# ProDocument_N64_SpyDVI_QSB_Compat_2024-0.net
KiCad netlist of a schematic drawn in EasyEDA Pro
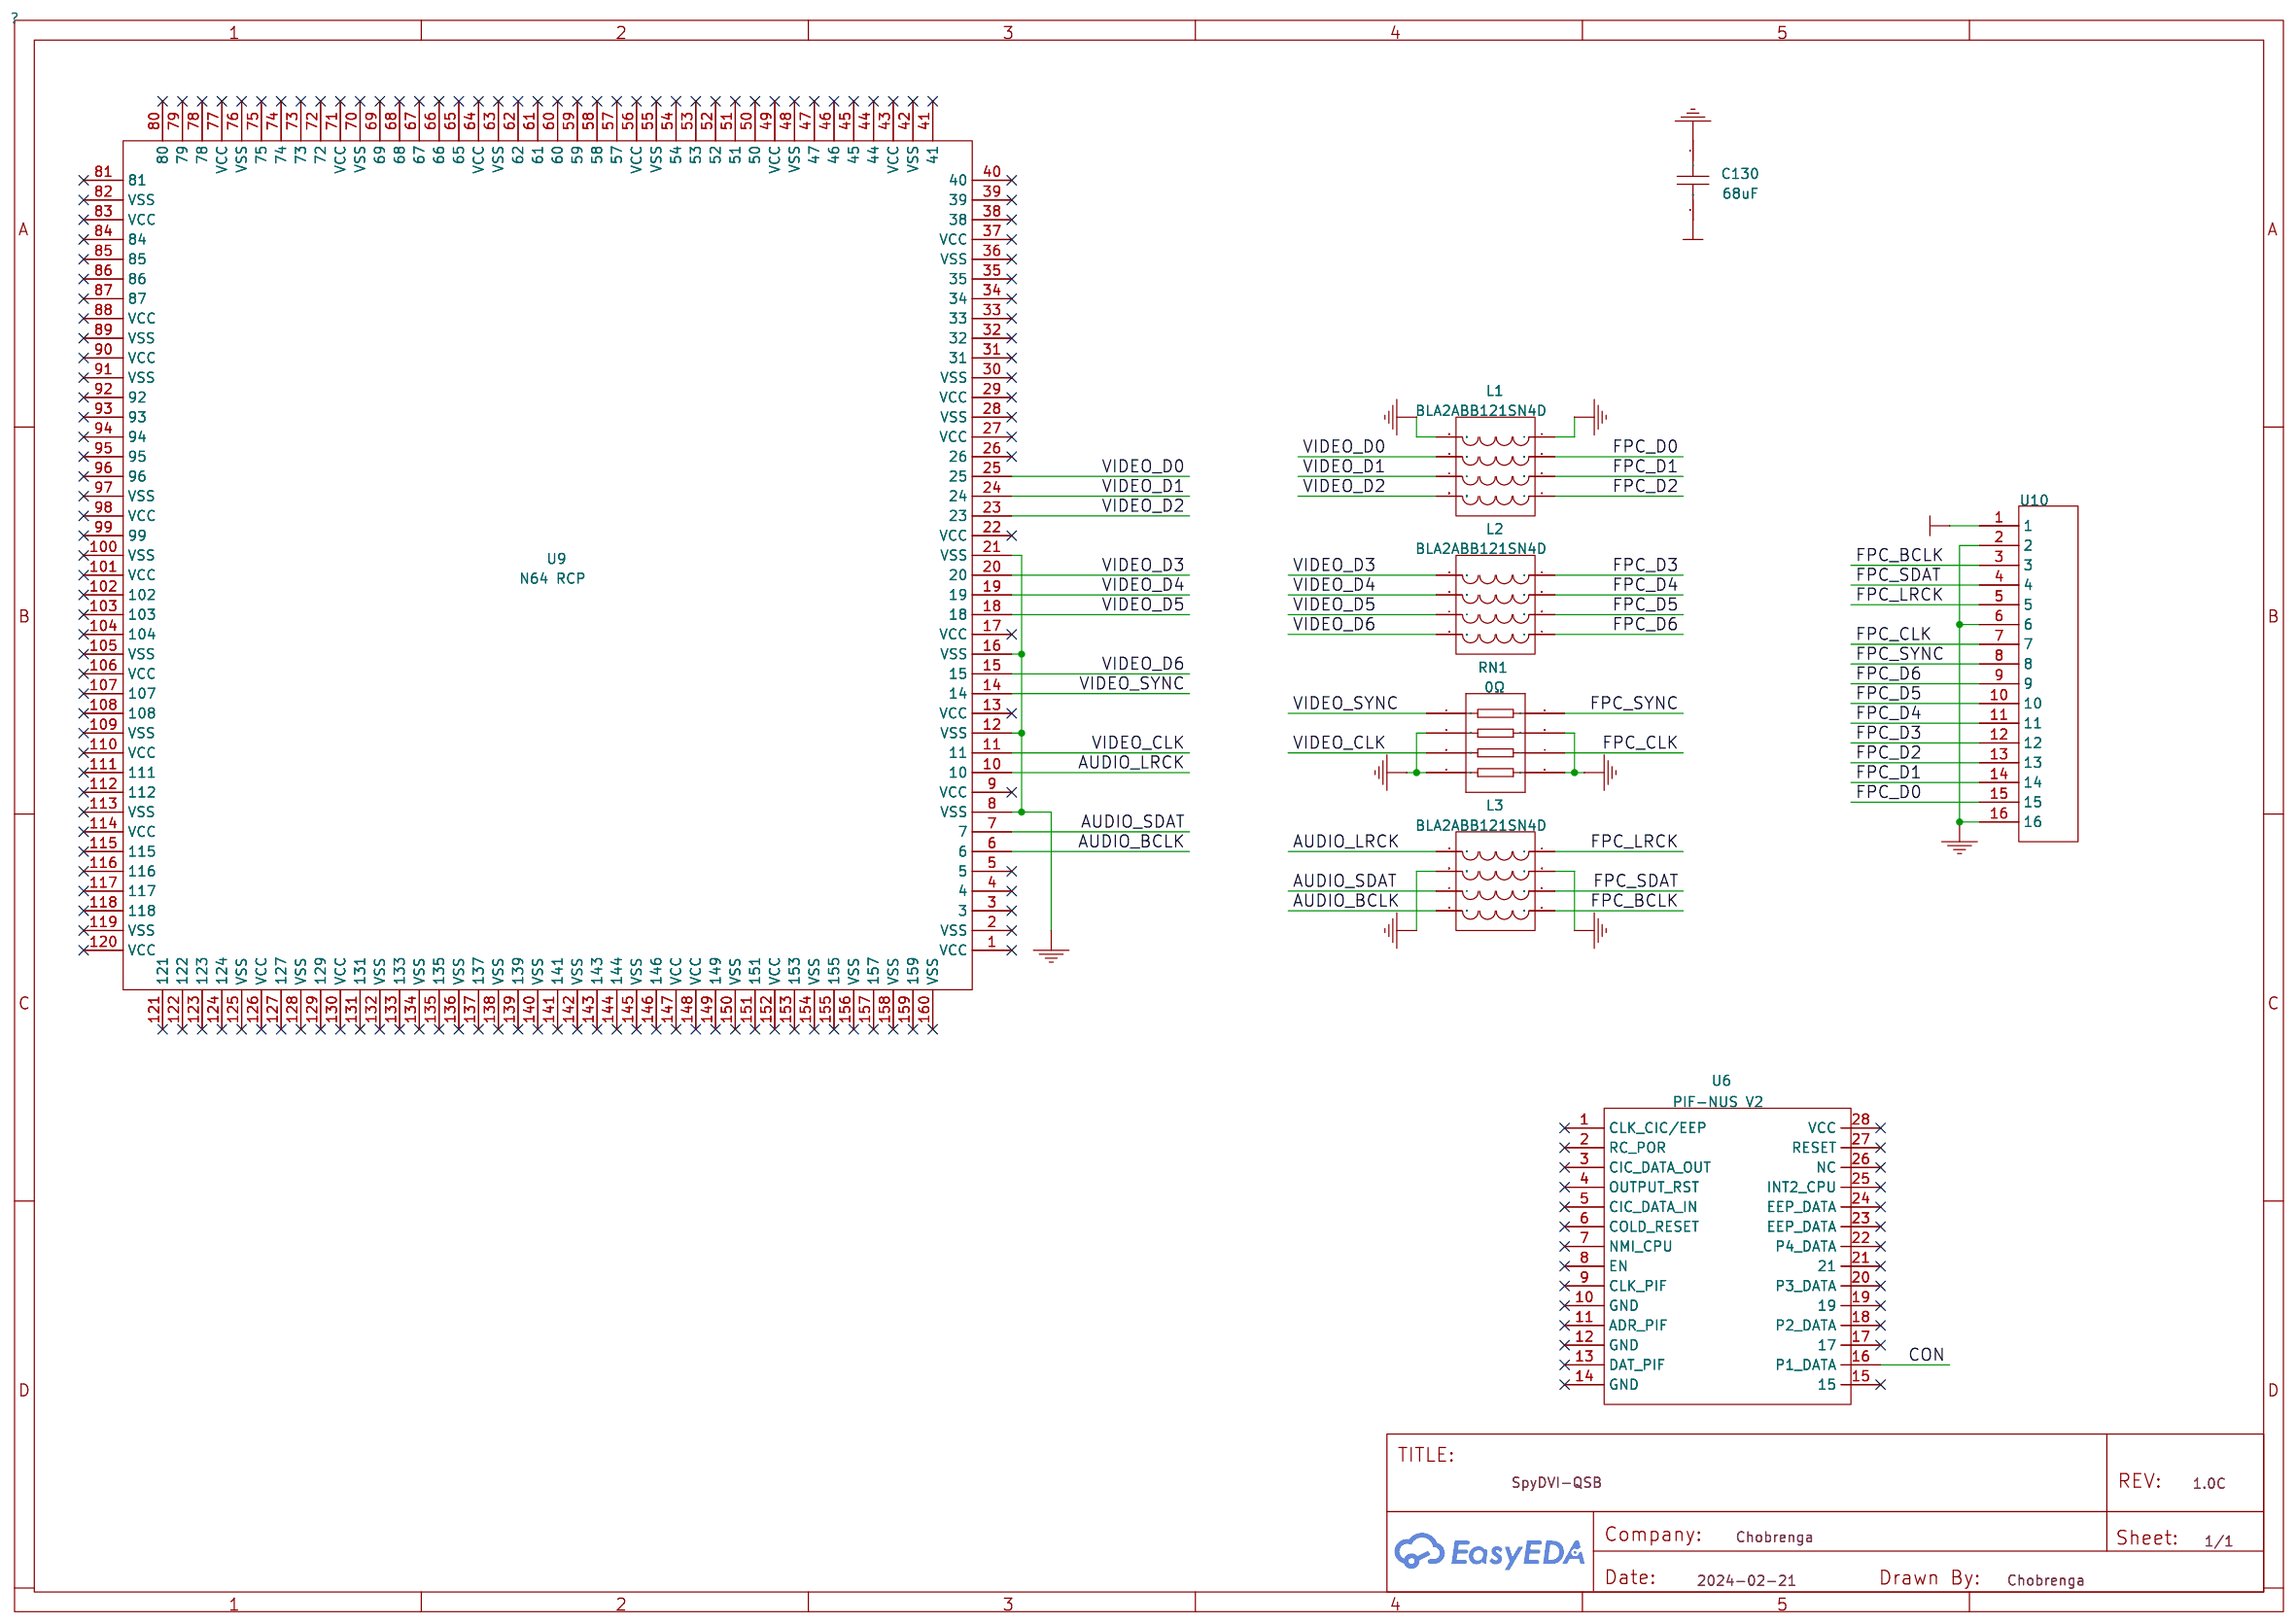
[diagram p0: schematic sheet]

(export (version "E")
  (design (tool "Eeschema 10.0.6"))
  (components
    (comp (ref "C130") (value "68uF") (libsource (lib "easyedapro") (part "68uF")))
    (comp (ref "L1")
      (value "BLA2ABB121SN4D")
      (footprint "easyedapro:BEAD-SMD_8P-L2.0-W1.0-P0.50-TL")
      (fields (field (name "Manufacturer") "muRata(村田)"))
      (libsource (lib "easyedapro") (part "BLA2ABB121SN4D"))
    )
    (comp (ref "L2")
      (value "BLA2ABB121SN4D")
      (footprint "easyedapro:BEAD-SMD_8P-L2.0-W1.0-P0.50-TL")
      (fields (field (name "Manufacturer") "muRata(村田)"))
      (libsource (lib "easyedapro") (part "BLA2ABB121SN4D"))
    )
    (comp (ref "L3")
      (value "BLA2ABB121SN4D")
      (footprint "easyedapro:BEAD-SMD_8P-L2.0-W1.0-P0.50-TL")
      (fields (field (name "Manufacturer") "muRata(村田)"))
      (libsource (lib "easyedapro") (part "BLA2ABB121SN4D"))
    )
    (comp (ref "RN1")
      (value "0Ω")
      (footprint "easyedapro:RES-ARRAY-SMD_0402-8P-L2.0-W1.0-BL")
      (fields (field (name "Manufacturer Part") "RC-MT08W000JT") (field (name "Manufacturer") "FH(风华)"))
      (libsource (lib "easyedapro") (part "0Ω"))
    )
    (comp (ref "U6") (value "PIF-NUS V2") (libsource (lib "easyedapro") (part "PIF-NUS V2")))
    (comp (ref "U9")
      (value "N64 RCP")
      (footprint "easyedapro:RCP NUS")
      (libsource (lib "easyedapro") (part "N64 RCP"))
    )
    (comp (ref "U10")
      (value "~")
      (description "For : AFA01-S16FCA-00")
      (libsource (lib "easyedapro") (part "16P_Ribbon"))
    )
  )
  (nets
    (net (code "1") (name "+5V") (class "Default")
      (node (ref "C130") (pin "2") (pinfunction "2_2") (pintype "unspecified"))
      (node (ref "U10") (pin "1") (pinfunction "1_1") (pintype "input"))
    )
    (net (code "2") (name "/AUDIO_BCLK") (class "Default")
      (node (ref "L3") (pin "8") (pinfunction "8_8") (pintype "unspecified"))
      (node (ref "U9") (pin "6") (pinfunction "6_6") (pintype "unspecified"))
    )
    (net (code "3") (name "/AUDIO_LRCK") (class "Default")
      (node (ref "L3") (pin "5") (pinfunction "5_5") (pintype "unspecified"))
      (node (ref "U9") (pin "10") (pinfunction "10_10") (pintype "unspecified"))
    )
    (net (code "4") (name "/AUDIO_SDAT") (class "Default")
      (node (ref "L3") (pin "7") (pinfunction "7_7") (pintype "unspecified"))
      (node (ref "U9") (pin "7") (pinfunction "7_7") (pintype "unspecified"))
    )
    (net (code "5") (name "/CON") (class "Default")
      (node (ref "U6") (pin "16") (pinfunction "P1_DATA_16") (pintype "unspecified"))
    )
    (net (code "6") (name "/FPC_BCLK") (class "Default")
      (node (ref "L3") (pin "1") (pinfunction "1_1") (pintype "unspecified"))
      (node (ref "U10") (pin "3") (pinfunction "3_3") (pintype "input"))
    )
    (net (code "7") (name "/FPC_CLK") (class "Default")
      (node (ref "RN1") (pin "7") (pinfunction "7_7") (pintype "input"))
      (node (ref "U10") (pin "7") (pinfunction "7_7") (pintype "input"))
    )
    (net (code "8") (name "/FPC_D0") (class "Default")
      (node (ref "L1") (pin "3") (pinfunction "3_3") (pintype "unspecified"))
      (node (ref "U10") (pin "15") (pinfunction "15_15") (pintype "input"))
    )
    (net (code "9") (name "/FPC_D1") (class "Default")
      (node (ref "L1") (pin "2") (pinfunction "2_2") (pintype "unspecified"))
      (node (ref "U10") (pin "14") (pinfunction "14_14") (pintype "input"))
    )
    (net (code "10") (name "/FPC_D2") (class "Default")
      (node (ref "L1") (pin "1") (pinfunction "1_1") (pintype "unspecified"))
      (node (ref "U10") (pin "13") (pinfunction "13_13") (pintype "input"))
    )
    (net (code "11") (name "/FPC_D3") (class "Default")
      (node (ref "L2") (pin "4") (pinfunction "4_4") (pintype "unspecified"))
      (node (ref "U10") (pin "12") (pinfunction "12_12") (pintype "input"))
    )
    (net (code "12") (name "/FPC_D4") (class "Default")
      (node (ref "L2") (pin "3") (pinfunction "3_3") (pintype "unspecified"))
      (node (ref "U10") (pin "11") (pinfunction "11_11") (pintype "input"))
    )
    (net (code "13") (name "/FPC_D5") (class "Default")
      (node (ref "L2") (pin "2") (pinfunction "2_2") (pintype "unspecified"))
      (node (ref "U10") (pin "10") (pinfunction "10_10") (pintype "input"))
    )
    (net (code "14") (name "/FPC_D6") (class "Default")
      (node (ref "L2") (pin "1") (pinfunction "1_1") (pintype "unspecified"))
      (node (ref "U10") (pin "9") (pinfunction "9_9") (pintype "input"))
    )
    (net (code "15") (name "/FPC_LRCK") (class "Default")
      (node (ref "L3") (pin "4") (pinfunction "4_4") (pintype "unspecified"))
      (node (ref "U10") (pin "5") (pinfunction "5_5") (pintype "input"))
    )
    (net (code "16") (name "/FPC_SDAT") (class "Default")
      (node (ref "L3") (pin "2") (pinfunction "2_2") (pintype "unspecified"))
      (node (ref "U10") (pin "4") (pinfunction "4_4") (pintype "input"))
    )
    (net (code "17") (name "/FPC_SYNC") (class "Default")
      (node (ref "RN1") (pin "5") (pinfunction "5_5") (pintype "input"))
      (node (ref "U10") (pin "8") (pinfunction "8_8") (pintype "input"))
    )
    (net (code "18") (name "/VIDEO_CLK") (class "Default")
      (node (ref "RN1") (pin "2") (pinfunction "2_2") (pintype "input"))
      (node (ref "U9") (pin "11") (pinfunction "11_11") (pintype "unspecified"))
    )
    (net (code "19") (name "/VIDEO_D0") (class "Default")
      (node (ref "L1") (pin "6") (pinfunction "6_6") (pintype "unspecified"))
      (node (ref "U9") (pin "25") (pinfunction "25_25") (pintype "unspecified"))
    )
    (net (code "20") (name "/VIDEO_D1") (class "Default")
      (node (ref "L1") (pin "7") (pinfunction "7_7") (pintype "unspecified"))
      (node (ref "U9") (pin "24") (pinfunction "24_24") (pintype "unspecified"))
    )
    (net (code "21") (name "/VIDEO_D2") (class "Default")
      (node (ref "L1") (pin "8") (pinfunction "8_8") (pintype "unspecified"))
      (node (ref "U9") (pin "23") (pinfunction "23_23") (pintype "unspecified"))
    )
    (net (code "22") (name "/VIDEO_D3") (class "Default")
      (node (ref "L2") (pin "5") (pinfunction "5_5") (pintype "unspecified"))
      (node (ref "U9") (pin "20") (pinfunction "20_20") (pintype "unspecified"))
    )
    (net (code "23") (name "/VIDEO_D4") (class "Default")
      (node (ref "L2") (pin "6") (pinfunction "6_6") (pintype "unspecified"))
      (node (ref "U9") (pin "19") (pinfunction "19_19") (pintype "unspecified"))
    )
    (net (code "24") (name "/VIDEO_D5") (class "Default")
      (node (ref "L2") (pin "7") (pinfunction "7_7") (pintype "unspecified"))
      (node (ref "U9") (pin "18") (pinfunction "18_18") (pintype "unspecified"))
    )
    (net (code "25") (name "/VIDEO_D6") (class "Default")
      (node (ref "L2") (pin "8") (pinfunction "8_8") (pintype "unspecified"))
      (node (ref "U9") (pin "15") (pinfunction "15_15") (pintype "unspecified"))
    )
    (net (code "26") (name "/VIDEO_SYNC") (class "Default")
      (node (ref "RN1") (pin "4") (pinfunction "4_4") (pintype "input"))
      (node (ref "U9") (pin "14") (pinfunction "14_14") (pintype "unspecified"))
    )
    (net (code "27") (name "GND") (class "Default")
      (node (ref "C130") (pin "1") (pinfunction "1_1") (pintype "unspecified"))
      (node (ref "L1") (pin "4") (pinfunction "4_4") (pintype "unspecified"))
      (node (ref "L1") (pin "5") (pinfunction "5_5") (pintype "unspecified"))
      (node (ref "L3") (pin "3") (pinfunction "3_3") (pintype "unspecified"))
      (node (ref "L3") (pin "6") (pinfunction "6_6") (pintype "unspecified"))
      (node (ref "RN1") (pin "1") (pinfunction "1_1") (pintype "input"))
      (node (ref "RN1") (pin "3") (pinfunction "3_3") (pintype "input"))
      (node (ref "RN1") (pin "6") (pinfunction "6_6") (pintype "input"))
      (node (ref "RN1") (pin "8") (pinfunction "8_8") (pintype "input"))
      (node (ref "U10") (pin "16") (pinfunction "16_16") (pintype "input"))
      (node (ref "U10") (pin "2") (pinfunction "2_2") (pintype "input"))
      (node (ref "U10") (pin "6") (pinfunction "6_6") (pintype "input"))
      (node (ref "U9") (pin "12") (pinfunction "VSS_12") (pintype "unspecified"))
      (node (ref "U9") (pin "16") (pinfunction "VSS_16") (pintype "unspecified"))
      (node (ref "U9") (pin "21") (pinfunction "VSS_21") (pintype "unspecified"))
      (node (ref "U9") (pin "8") (pinfunction "VSS_8") (pintype "unspecified"))
    )
    (net (code "28") (name "unconnected-(U6-ADR_PIF-Pad11)") (class "Default")
      (node (ref "U6") (pin "11") (pinfunction "ADR_PIF_11") (pintype "unspecified+no_connect"))
    )
    (net (code "29") (name "unconnected-(U6-CIC_DATA_IN-Pad5)") (class "Default")
      (node (ref "U6") (pin "5") (pinfunction "CIC_DATA_IN_5") (pintype "unspecified+no_connect"))
    )
    (net (code "30") (name "unconnected-(U6-CIC_DATA_OUT-Pad3)") (class "Default")
      (node (ref "U6") (pin "3") (pinfunction "CIC_DATA_OUT_3") (pintype "unspecified+no_connect"))
    )
    (net (code "31") (name "unconnected-(U6-CLK_CIC{slash}EEP-Pad1)") (class "Default")
      (node (ref "U6") (pin "1") (pinfunction "CLK_CIC/EEP_1") (pintype "unspecified+no_connect"))
    )
    (net (code "32") (name "unconnected-(U6-CLK_PIF-Pad9)") (class "Default")
      (node (ref "U6") (pin "9") (pinfunction "CLK_PIF_9") (pintype "unspecified+no_connect"))
    )
    (net (code "33") (name "unconnected-(U6-COLD_RESET-Pad6)") (class "Default")
      (node (ref "U6") (pin "6") (pinfunction "COLD_RESET_6") (pintype "unspecified+no_connect"))
    )
    (net (code "34") (name "unconnected-(U6-DAT_PIF-Pad13)") (class "Default")
      (node (ref "U6") (pin "13") (pinfunction "DAT_PIF_13") (pintype "unspecified+no_connect"))
    )
    (net (code "35") (name "unconnected-(U6-EEP_DATA-Pad23)") (class "Default")
      (node (ref "U6") (pin "23") (pinfunction "EEP_DATA_23") (pintype "unspecified+no_connect"))
    )
    (net (code "36") (name "unconnected-(U6-EEP_DATA-Pad24)") (class "Default")
      (node (ref "U6") (pin "24") (pinfunction "EEP_DATA_24") (pintype "unspecified+no_connect"))
    )
    (net (code "37") (name "unconnected-(U6-EN-Pad8)") (class "Default")
      (node (ref "U6") (pin "8") (pinfunction "EN_8") (pintype "unspecified+no_connect"))
    )
    (net (code "38") (name "unconnected-(U6-GND-Pad10)") (class "Default")
      (node (ref "U6") (pin "10") (pinfunction "GND_10") (pintype "unspecified+no_connect"))
    )
    (net (code "39") (name "unconnected-(U6-GND-Pad12)") (class "Default")
      (node (ref "U6") (pin "12") (pinfunction "GND_12") (pintype "unspecified+no_connect"))
    )
    (net (code "40") (name "unconnected-(U6-GND-Pad14)") (class "Default")
      (node (ref "U6") (pin "14") (pinfunction "GND_14") (pintype "unspecified+no_connect"))
    )
    (net (code "41") (name "unconnected-(U6-INT2_CPU-Pad25)") (class "Default")
      (node (ref "U6") (pin "25") (pinfunction "INT2_CPU_25") (pintype "unspecified+no_connect"))
    )
    (net (code "42") (name "unconnected-(U6-NC-Pad26)") (class "Default")
      (node (ref "U6") (pin "26") (pinfunction "NC_26") (pintype "unspecified+no_connect"))
    )
    (net (code "43") (name "unconnected-(U6-NMI_CPU-Pad7)") (class "Default")
      (node (ref "U6") (pin "7") (pinfunction "NMI_CPU_7") (pintype "unspecified+no_connect"))
    )
    (net (code "44") (name "unconnected-(U6-OUTPUT_RST-Pad4)") (class "Default")
      (node (ref "U6") (pin "4") (pinfunction "OUTPUT_RST_4") (pintype "unspecified+no_connect"))
    )
    (net (code "45") (name "unconnected-(U6-P2_DATA-Pad18)") (class "Default")
      (node (ref "U6") (pin "18") (pinfunction "P2_DATA_18") (pintype "unspecified+no_connect"))
    )
    (net (code "46") (name "unconnected-(U6-P3_DATA-Pad20)") (class "Default")
      (node (ref "U6") (pin "20") (pinfunction "P3_DATA_20") (pintype "unspecified+no_connect"))
    )
    (net (code "47") (name "unconnected-(U6-P4_DATA-Pad22)") (class "Default")
      (node (ref "U6") (pin "22") (pinfunction "P4_DATA_22") (pintype "unspecified+no_connect"))
    )
    (net (code "48") (name "unconnected-(U6-Pad15)") (class "Default")
      (node (ref "U6") (pin "15") (pinfunction "15_15") (pintype "unspecified+no_connect"))
    )
    (net (code "49") (name "unconnected-(U6-Pad17)") (class "Default")
      (node (ref "U6") (pin "17") (pinfunction "17_17") (pintype "unspecified+no_connect"))
    )
    (net (code "50") (name "unconnected-(U6-Pad19)") (class "Default")
      (node (ref "U6") (pin "19") (pinfunction "19_19") (pintype "unspecified+no_connect"))
    )
    (net (code "51") (name "unconnected-(U6-Pad21)") (class "Default")
      (node (ref "U6") (pin "21") (pinfunction "21_21") (pintype "unspecified+no_connect"))
    )
    (net (code "52") (name "unconnected-(U6-RC_POR-Pad2)") (class "Default")
      (node (ref "U6") (pin "2") (pinfunction "RC_POR_2") (pintype "unspecified+no_connect"))
    )
    (net (code "53") (name "unconnected-(U6-RESET-Pad27)") (class "Default")
      (node (ref "U6") (pin "27") (pinfunction "RESET_27") (pintype "unspecified+no_connect"))
    )
    (net (code "54") (name "unconnected-(U6-VCC-Pad28)") (class "Default")
      (node (ref "U6") (pin "28") (pinfunction "VCC_28") (pintype "unspecified+no_connect"))
    )
    (net (code "55") (name "unconnected-(U9-Pad3)") (class "Default")
      (node (ref "U9") (pin "3") (pinfunction "3_3") (pintype "unspecified+no_connect"))
    )
    (net (code "56") (name "unconnected-(U9-Pad4)") (class "Default")
      (node (ref "U9") (pin "4") (pinfunction "4_4") (pintype "unspecified+no_connect"))
    )
    (net (code "57") (name "unconnected-(U9-Pad5)") (class "Default")
      (node (ref "U9") (pin "5") (pinfunction "5_5") (pintype "unspecified+no_connect"))
    )
    (net (code "58") (name "unconnected-(U9-Pad26)") (class "Default")
      (node (ref "U9") (pin "26") (pinfunction "26_26") (pintype "unspecified+no_connect"))
    )
    (net (code "59") (name "unconnected-(U9-Pad31)") (class "Default")
      (node (ref "U9") (pin "31") (pinfunction "31_31") (pintype "unspecified+no_connect"))
    )
    (net (code "60") (name "unconnected-(U9-Pad32)") (class "Default")
      (node (ref "U9") (pin "32") (pinfunction "32_32") (pintype "unspecified+no_connect"))
    )
    (net (code "61") (name "unconnected-(U9-Pad33)") (class "Default")
      (node (ref "U9") (pin "33") (pinfunction "33_33") (pintype "unspecified+no_connect"))
    )
    (net (code "62") (name "unconnected-(U9-Pad34)") (class "Default")
      (node (ref "U9") (pin "34") (pinfunction "34_34") (pintype "unspecified+no_connect"))
    )
    (net (code "63") (name "unconnected-(U9-Pad35)") (class "Default")
      (node (ref "U9") (pin "35") (pinfunction "35_35") (pintype "unspecified+no_connect"))
    )
    (net (code "64") (name "unconnected-(U9-Pad38)") (class "Default")
      (node (ref "U9") (pin "38") (pinfunction "38_38") (pintype "unspecified+no_connect"))
    )
    (net (code "65") (name "unconnected-(U9-Pad39)") (class "Default")
      (node (ref "U9") (pin "39") (pinfunction "39_39") (pintype "unspecified+no_connect"))
    )
    (net (code "66") (name "unconnected-(U9-Pad40)") (class "Default")
      (node (ref "U9") (pin "40") (pinfunction "40_40") (pintype "unspecified+no_connect"))
    )
    (net (code "67") (name "unconnected-(U9-Pad41)") (class "Default")
      (node (ref "U9") (pin "41") (pinfunction "41_41") (pintype "unspecified+no_connect"))
    )
    (net (code "68") (name "unconnected-(U9-Pad44)") (class "Default")
      (node (ref "U9") (pin "44") (pinfunction "44_44") (pintype "unspecified+no_connect"))
    )
    (net (code "69") (name "unconnected-(U9-Pad45)") (class "Default")
      (node (ref "U9") (pin "45") (pinfunction "45_45") (pintype "unspecified+no_connect"))
    )
    (net (code "70") (name "unconnected-(U9-Pad46)") (class "Default")
      (node (ref "U9") (pin "46") (pinfunction "46_46") (pintype "unspecified+no_connect"))
    )
    (net (code "71") (name "unconnected-(U9-Pad47)") (class "Default")
      (node (ref "U9") (pin "47") (pinfunction "47_47") (pintype "unspecified+no_connect"))
    )
    (net (code "72") (name "unconnected-(U9-Pad50)") (class "Default")
      (node (ref "U9") (pin "50") (pinfunction "50_50") (pintype "unspecified+no_connect"))
    )
    (net (code "73") (name "unconnected-(U9-Pad51)") (class "Default")
      (node (ref "U9") (pin "51") (pinfunction "51_51") (pintype "unspecified+no_connect"))
    )
    (net (code "74") (name "unconnected-(U9-Pad52)") (class "Default")
      (node (ref "U9") (pin "52") (pinfunction "52_52") (pintype "unspecified+no_connect"))
    )
    (net (code "75") (name "unconnected-(U9-Pad53)") (class "Default")
      (node (ref "U9") (pin "53") (pinfunction "53_53") (pintype "unspecified+no_connect"))
    )
    (net (code "76") (name "unconnected-(U9-Pad54)") (class "Default")
      (node (ref "U9") (pin "54") (pinfunction "54_54") (pintype "unspecified+no_connect"))
    )
    (net (code "77") (name "unconnected-(U9-Pad57)") (class "Default")
      (node (ref "U9") (pin "57") (pinfunction "57_57") (pintype "unspecified+no_connect"))
    )
    (net (code "78") (name "unconnected-(U9-Pad58)") (class "Default")
      (node (ref "U9") (pin "58") (pinfunction "58_58") (pintype "unspecified+no_connect"))
    )
    (net (code "79") (name "unconnected-(U9-Pad59)") (class "Default")
      (node (ref "U9") (pin "59") (pinfunction "59_59") (pintype "unspecified+no_connect"))
    )
    (net (code "80") (name "unconnected-(U9-Pad60)") (class "Default")
      (node (ref "U9") (pin "60") (pinfunction "60_60") (pintype "unspecified+no_connect"))
    )
    (net (code "81") (name "unconnected-(U9-Pad61)") (class "Default")
      (node (ref "U9") (pin "61") (pinfunction "61_61") (pintype "unspecified+no_connect"))
    )
    (net (code "82") (name "unconnected-(U9-Pad62)") (class "Default")
      (node (ref "U9") (pin "62") (pinfunction "62_62") (pintype "unspecified+no_connect"))
    )
    (net (code "83") (name "unconnected-(U9-Pad65)") (class "Default")
      (node (ref "U9") (pin "65") (pinfunction "65_65") (pintype "unspecified+no_connect"))
    )
    (net (code "84") (name "unconnected-(U9-Pad66)") (class "Default")
      (node (ref "U9") (pin "66") (pinfunction "66_66") (pintype "unspecified+no_connect"))
    )
    (net (code "85") (name "unconnected-(U9-Pad67)") (class "Default")
      (node (ref "U9") (pin "67") (pinfunction "67_67") (pintype "unspecified+no_connect"))
    )
    (net (code "86") (name "unconnected-(U9-Pad68)") (class "Default")
      (node (ref "U9") (pin "68") (pinfunction "68_68") (pintype "unspecified+no_connect"))
    )
    (net (code "87") (name "unconnected-(U9-Pad69)") (class "Default")
      (node (ref "U9") (pin "69") (pinfunction "69_69") (pintype "unspecified+no_connect"))
    )
    (net (code "88") (name "unconnected-(U9-Pad72)") (class "Default")
      (node (ref "U9") (pin "72") (pinfunction "72_72") (pintype "unspecified+no_connect"))
    )
    (net (code "89") (name "unconnected-(U9-Pad73)") (class "Default")
      (node (ref "U9") (pin "73") (pinfunction "73_73") (pintype "unspecified+no_connect"))
    )
    (net (code "90") (name "unconnected-(U9-Pad74)") (class "Default")
      (node (ref "U9") (pin "74") (pinfunction "74_74") (pintype "unspecified+no_connect"))
    )
    (net (code "91") (name "unconnected-(U9-Pad75)") (class "Default")
      (node (ref "U9") (pin "75") (pinfunction "75_75") (pintype "unspecified+no_connect"))
    )
    (net (code "92") (name "unconnected-(U9-Pad78)") (class "Default")
      (node (ref "U9") (pin "78") (pinfunction "78_78") (pintype "unspecified+no_connect"))
    )
    (net (code "93") (name "unconnected-(U9-Pad79)") (class "Default")
      (node (ref "U9") (pin "79") (pinfunction "79_79") (pintype "unspecified+no_connect"))
    )
    (net (code "94") (name "unconnected-(U9-Pad80)") (class "Default")
      (node (ref "U9") (pin "80") (pinfunction "80_80") (pintype "unspecified+no_connect"))
    )
    (net (code "95") (name "unconnected-(U9-Pad81)") (class "Default")
      (node (ref "U9") (pin "81") (pinfunction "81_81") (pintype "unspecified+no_connect"))
    )
    (net (code "96") (name "unconnected-(U9-Pad84)") (class "Default")
      (node (ref "U9") (pin "84") (pinfunction "84_84") (pintype "unspecified+no_connect"))
    )
    (net (code "97") (name "unconnected-(U9-Pad85)") (class "Default")
      (node (ref "U9") (pin "85") (pinfunction "85_85") (pintype "unspecified+no_connect"))
    )
    (net (code "98") (name "unconnected-(U9-Pad86)") (class "Default")
      (node (ref "U9") (pin "86") (pinfunction "86_86") (pintype "unspecified+no_connect"))
    )
    (net (code "99") (name "unconnected-(U9-Pad87)") (class "Default")
      (node (ref "U9") (pin "87") (pinfunction "87_87") (pintype "unspecified+no_connect"))
    )
    (net (code "100") (name "unconnected-(U9-Pad92)") (class "Default")
      (node (ref "U9") (pin "92") (pinfunction "92_92") (pintype "unspecified+no_connect"))
    )
    (net (code "101") (name "unconnected-(U9-Pad93)") (class "Default")
      (node (ref "U9") (pin "93") (pinfunction "93_93") (pintype "unspecified+no_connect"))
    )
    (net (code "102") (name "unconnected-(U9-Pad94)") (class "Default")
      (node (ref "U9") (pin "94") (pinfunction "94_94") (pintype "unspecified+no_connect"))
    )
    (net (code "103") (name "unconnected-(U9-Pad95)") (class "Default")
      (node (ref "U9") (pin "95") (pinfunction "95_95") (pintype "unspecified+no_connect"))
    )
    (net (code "104") (name "unconnected-(U9-Pad96)") (class "Default")
      (node (ref "U9") (pin "96") (pinfunction "96_96") (pintype "unspecified+no_connect"))
    )
    (net (code "105") (name "unconnected-(U9-Pad99)") (class "Default")
      (node (ref "U9") (pin "99") (pinfunction "99_99") (pintype "unspecified+no_connect"))
    )
    (net (code "106") (name "unconnected-(U9-Pad102)") (class "Default")
      (node (ref "U9") (pin "102") (pinfunction "102_102") (pintype "unspecified+no_connect"))
    )
    (net (code "107") (name "unconnected-(U9-Pad103)") (class "Default")
      (node (ref "U9") (pin "103") (pinfunction "103_103") (pintype "unspecified+no_connect"))
    )
    (net (code "108") (name "unconnected-(U9-Pad104)") (class "Default")
      (node (ref "U9") (pin "104") (pinfunction "104_104") (pintype "unspecified+no_connect"))
    )
    (net (code "109") (name "unconnected-(U9-Pad107)") (class "Default")
      (node (ref "U9") (pin "107") (pinfunction "107_107") (pintype "unspecified+no_connect"))
    )
    (net (code "110") (name "unconnected-(U9-Pad108)") (class "Default")
      (node (ref "U9") (pin "108") (pinfunction "108_108") (pintype "unspecified+no_connect"))
    )
    (net (code "111") (name "unconnected-(U9-Pad111)") (class "Default")
      (node (ref "U9") (pin "111") (pinfunction "111_111") (pintype "unspecified+no_connect"))
    )
    (net (code "112") (name "unconnected-(U9-Pad112)") (class "Default")
      (node (ref "U9") (pin "112") (pinfunction "112_112") (pintype "unspecified+no_connect"))
    )
    (net (code "113") (name "unconnected-(U9-Pad115)") (class "Default")
      (node (ref "U9") (pin "115") (pinfunction "115_115") (pintype "unspecified+no_connect"))
    )
    (net (code "114") (name "unconnected-(U9-Pad116)") (class "Default")
      (node (ref "U9") (pin "116") (pinfunction "116_116") (pintype "unspecified+no_connect"))
    )
    (net (code "115") (name "unconnected-(U9-Pad117)") (class "Default")
      (node (ref "U9") (pin "117") (pinfunction "117_117") (pintype "unspecified+no_connect"))
    )
    (net (code "116") (name "unconnected-(U9-Pad118)") (class "Default")
      (node (ref "U9") (pin "118") (pinfunction "118_118") (pintype "unspecified+no_connect"))
    )
    (net (code "117") (name "unconnected-(U9-Pad121)") (class "Default")
      (node (ref "U9") (pin "121") (pinfunction "121_121") (pintype "unspecified+no_connect"))
    )
    (net (code "118") (name "unconnected-(U9-Pad122)") (class "Default")
      (node (ref "U9") (pin "122") (pinfunction "122_122") (pintype "unspecified+no_connect"))
    )
    (net (code "119") (name "unconnected-(U9-Pad123)") (class "Default")
      (node (ref "U9") (pin "123") (pinfunction "123_123") (pintype "unspecified+no_connect"))
    )
    (net (code "120") (name "unconnected-(U9-Pad124)") (class "Default")
      (node (ref "U9") (pin "124") (pinfunction "124_124") (pintype "unspecified+no_connect"))
    )
    (net (code "121") (name "unconnected-(U9-Pad127)") (class "Default")
      (node (ref "U9") (pin "127") (pinfunction "127_127") (pintype "unspecified+no_connect"))
    )
    (net (code "122") (name "unconnected-(U9-Pad129)") (class "Default")
      (node (ref "U9") (pin "129") (pinfunction "129_129") (pintype "unspecified+no_connect"))
    )
    (net (code "123") (name "unconnected-(U9-Pad131)") (class "Default")
      (node (ref "U9") (pin "131") (pinfunction "131_131") (pintype "unspecified+no_connect"))
    )
    (net (code "124") (name "unconnected-(U9-Pad133)") (class "Default")
      (node (ref "U9") (pin "133") (pinfunction "133_133") (pintype "unspecified+no_connect"))
    )
    (net (code "125") (name "unconnected-(U9-Pad135)") (class "Default")
      (node (ref "U9") (pin "135") (pinfunction "135_135") (pintype "unspecified+no_connect"))
    )
    (net (code "126") (name "unconnected-(U9-Pad137)") (class "Default")
      (node (ref "U9") (pin "137") (pinfunction "137_137") (pintype "unspecified+no_connect"))
    )
    (net (code "127") (name "unconnected-(U9-Pad139)") (class "Default")
      (node (ref "U9") (pin "139") (pinfunction "139_139") (pintype "unspecified+no_connect"))
    )
    (net (code "128") (name "unconnected-(U9-Pad141)") (class "Default")
      (node (ref "U9") (pin "141") (pinfunction "141_141") (pintype "unspecified+no_connect"))
    )
    (net (code "129") (name "unconnected-(U9-Pad143)") (class "Default")
      (node (ref "U9") (pin "143") (pinfunction "143_143") (pintype "unspecified+no_connect"))
    )
    (net (code "130") (name "unconnected-(U9-Pad144)") (class "Default")
      (node (ref "U9") (pin "144") (pinfunction "144_144") (pintype "unspecified+no_connect"))
    )
    (net (code "131") (name "unconnected-(U9-Pad146)") (class "Default")
      (node (ref "U9") (pin "146") (pinfunction "146_146") (pintype "unspecified+no_connect"))
    )
    (net (code "132") (name "unconnected-(U9-Pad149)") (class "Default")
      (node (ref "U9") (pin "149") (pinfunction "149_149") (pintype "unspecified+no_connect"))
    )
    (net (code "133") (name "unconnected-(U9-Pad151)") (class "Default")
      (node (ref "U9") (pin "151") (pinfunction "151_151") (pintype "unspecified+no_connect"))
    )
    (net (code "134") (name "unconnected-(U9-Pad153)") (class "Default")
      (node (ref "U9") (pin "153") (pinfunction "153_153") (pintype "unspecified+no_connect"))
    )
    (net (code "135") (name "unconnected-(U9-Pad155)") (class "Default")
      (node (ref "U9") (pin "155") (pinfunction "155_155") (pintype "unspecified+no_connect"))
    )
    (net (code "136") (name "unconnected-(U9-Pad157)") (class "Default")
      (node (ref "U9") (pin "157") (pinfunction "157_157") (pintype "unspecified+no_connect"))
    )
    (net (code "137") (name "unconnected-(U9-Pad159)") (class "Default")
      (node (ref "U9") (pin "159") (pinfunction "159_159") (pintype "unspecified+no_connect"))
    )
    (net (code "138") (name "unconnected-(U9-VCC-Pad1)") (class "Default")
      (node (ref "U9") (pin "1") (pinfunction "VCC_1") (pintype "unspecified+no_connect"))
    )
    (net (code "139") (name "unconnected-(U9-VCC-Pad9)") (class "Default")
      (node (ref "U9") (pin "9") (pinfunction "VCC_9") (pintype "unspecified+no_connect"))
    )
    (net (code "140") (name "unconnected-(U9-VCC-Pad13)") (class "Default")
      (node (ref "U9") (pin "13") (pinfunction "VCC_13") (pintype "unspecified+no_connect"))
    )
    (net (code "141") (name "unconnected-(U9-VCC-Pad17)") (class "Default")
      (node (ref "U9") (pin "17") (pinfunction "VCC_17") (pintype "unspecified+no_connect"))
    )
    (net (code "142") (name "unconnected-(U9-VCC-Pad22)") (class "Default")
      (node (ref "U9") (pin "22") (pinfunction "VCC_22") (pintype "unspecified+no_connect"))
    )
    (net (code "143") (name "unconnected-(U9-VCC-Pad27)") (class "Default")
      (node (ref "U9") (pin "27") (pinfunction "VCC_27") (pintype "unspecified+no_connect"))
    )
    (net (code "144") (name "unconnected-(U9-VCC-Pad29)") (class "Default")
      (node (ref "U9") (pin "29") (pinfunction "VCC_29") (pintype "unspecified+no_connect"))
    )
    (net (code "145") (name "unconnected-(U9-VCC-Pad37)") (class "Default")
      (node (ref "U9") (pin "37") (pinfunction "VCC_37") (pintype "unspecified+no_connect"))
    )
    (net (code "146") (name "unconnected-(U9-VCC-Pad43)") (class "Default")
      (node (ref "U9") (pin "43") (pinfunction "VCC_43") (pintype "unspecified+no_connect"))
    )
    (net (code "147") (name "unconnected-(U9-VCC-Pad49)") (class "Default")
      (node (ref "U9") (pin "49") (pinfunction "VCC_49") (pintype "unspecified+no_connect"))
    )
    (net (code "148") (name "unconnected-(U9-VCC-Pad56)") (class "Default")
      (node (ref "U9") (pin "56") (pinfunction "VCC_56") (pintype "unspecified+no_connect"))
    )
    (net (code "149") (name "unconnected-(U9-VCC-Pad64)") (class "Default")
      (node (ref "U9") (pin "64") (pinfunction "VCC_64") (pintype "unspecified+no_connect"))
    )
    (net (code "150") (name "unconnected-(U9-VCC-Pad71)") (class "Default")
      (node (ref "U9") (pin "71") (pinfunction "VCC_71") (pintype "unspecified+no_connect"))
    )
    (net (code "151") (name "unconnected-(U9-VCC-Pad77)") (class "Default")
      (node (ref "U9") (pin "77") (pinfunction "VCC_77") (pintype "unspecified+no_connect"))
    )
    (net (code "152") (name "unconnected-(U9-VCC-Pad83)") (class "Default")
      (node (ref "U9") (pin "83") (pinfunction "VCC_83") (pintype "unspecified+no_connect"))
    )
    (net (code "153") (name "unconnected-(U9-VCC-Pad88)") (class "Default")
      (node (ref "U9") (pin "88") (pinfunction "VCC_88") (pintype "unspecified+no_connect"))
    )
    (net (code "154") (name "unconnected-(U9-VCC-Pad90)") (class "Default")
      (node (ref "U9") (pin "90") (pinfunction "VCC_90") (pintype "unspecified+no_connect"))
    )
    (net (code "155") (name "unconnected-(U9-VCC-Pad98)") (class "Default")
      (node (ref "U9") (pin "98") (pinfunction "VCC_98") (pintype "unspecified+no_connect"))
    )
    (net (code "156") (name "unconnected-(U9-VCC-Pad101)") (class "Default")
      (node (ref "U9") (pin "101") (pinfunction "VCC_101") (pintype "unspecified+no_connect"))
    )
    (net (code "157") (name "unconnected-(U9-VCC-Pad106)") (class "Default")
      (node (ref "U9") (pin "106") (pinfunction "VCC_106") (pintype "unspecified+no_connect"))
    )
    (net (code "158") (name "unconnected-(U9-VCC-Pad110)") (class "Default")
      (node (ref "U9") (pin "110") (pinfunction "VCC_110") (pintype "unspecified+no_connect"))
    )
    (net (code "159") (name "unconnected-(U9-VCC-Pad114)") (class "Default")
      (node (ref "U9") (pin "114") (pinfunction "VCC_114") (pintype "unspecified+no_connect"))
    )
    (net (code "160") (name "unconnected-(U9-VCC-Pad120)") (class "Default")
      (node (ref "U9") (pin "120") (pinfunction "VCC_120") (pintype "unspecified+no_connect"))
    )
    (net (code "161") (name "unconnected-(U9-VCC-Pad126)") (class "Default")
      (node (ref "U9") (pin "126") (pinfunction "VCC_126") (pintype "unspecified+no_connect"))
    )
    (net (code "162") (name "unconnected-(U9-VCC-Pad130)") (class "Default")
      (node (ref "U9") (pin "130") (pinfunction "VCC_130") (pintype "unspecified+no_connect"))
    )
    (net (code "163") (name "unconnected-(U9-VCC-Pad147)") (class "Default")
      (node (ref "U9") (pin "147") (pinfunction "VCC_147") (pintype "unspecified+no_connect"))
    )
    (net (code "164") (name "unconnected-(U9-VCC-Pad148)") (class "Default")
      (node (ref "U9") (pin "148") (pinfunction "VCC_148") (pintype "unspecified+no_connect"))
    )
    (net (code "165") (name "unconnected-(U9-VCC-Pad152)") (class "Default")
      (node (ref "U9") (pin "152") (pinfunction "VCC_152") (pintype "unspecified+no_connect"))
    )
    (net (code "166") (name "unconnected-(U9-VSS-Pad2)") (class "Default")
      (node (ref "U9") (pin "2") (pinfunction "VSS_2") (pintype "unspecified+no_connect"))
    )
    (net (code "167") (name "unconnected-(U9-VSS-Pad28)") (class "Default")
      (node (ref "U9") (pin "28") (pinfunction "VSS_28") (pintype "unspecified+no_connect"))
    )
    (net (code "168") (name "unconnected-(U9-VSS-Pad30)") (class "Default")
      (node (ref "U9") (pin "30") (pinfunction "VSS_30") (pintype "unspecified+no_connect"))
    )
    (net (code "169") (name "unconnected-(U9-VSS-Pad36)") (class "Default")
      (node (ref "U9") (pin "36") (pinfunction "VSS_36") (pintype "unspecified+no_connect"))
    )
    (net (code "170") (name "unconnected-(U9-VSS-Pad42)") (class "Default")
      (node (ref "U9") (pin "42") (pinfunction "VSS_42") (pintype "unspecified+no_connect"))
    )
    (net (code "171") (name "unconnected-(U9-VSS-Pad48)") (class "Default")
      (node (ref "U9") (pin "48") (pinfunction "VSS_48") (pintype "unspecified+no_connect"))
    )
    (net (code "172") (name "unconnected-(U9-VSS-Pad55)") (class "Default")
      (node (ref "U9") (pin "55") (pinfunction "VSS_55") (pintype "unspecified+no_connect"))
    )
    (net (code "173") (name "unconnected-(U9-VSS-Pad63)") (class "Default")
      (node (ref "U9") (pin "63") (pinfunction "VSS_63") (pintype "unspecified+no_connect"))
    )
    (net (code "174") (name "unconnected-(U9-VSS-Pad70)") (class "Default")
      (node (ref "U9") (pin "70") (pinfunction "VSS_70") (pintype "unspecified+no_connect"))
    )
    (net (code "175") (name "unconnected-(U9-VSS-Pad76)") (class "Default")
      (node (ref "U9") (pin "76") (pinfunction "VSS_76") (pintype "unspecified+no_connect"))
    )
    (net (code "176") (name "unconnected-(U9-VSS-Pad82)") (class "Default")
      (node (ref "U9") (pin "82") (pinfunction "VSS_82") (pintype "unspecified+no_connect"))
    )
    (net (code "177") (name "unconnected-(U9-VSS-Pad89)") (class "Default")
      (node (ref "U9") (pin "89") (pinfunction "VSS_89") (pintype "unspecified+no_connect"))
    )
    (net (code "178") (name "unconnected-(U9-VSS-Pad91)") (class "Default")
      (node (ref "U9") (pin "91") (pinfunction "VSS_91") (pintype "unspecified+no_connect"))
    )
    (net (code "179") (name "unconnected-(U9-VSS-Pad97)") (class "Default")
      (node (ref "U9") (pin "97") (pinfunction "VSS_97") (pintype "unspecified+no_connect"))
    )
    (net (code "180") (name "unconnected-(U9-VSS-Pad100)") (class "Default")
      (node (ref "U9") (pin "100") (pinfunction "VSS_100") (pintype "unspecified+no_connect"))
    )
    (net (code "181") (name "unconnected-(U9-VSS-Pad105)") (class "Default")
      (node (ref "U9") (pin "105") (pinfunction "VSS_105") (pintype "unspecified+no_connect"))
    )
    (net (code "182") (name "unconnected-(U9-VSS-Pad109)") (class "Default")
      (node (ref "U9") (pin "109") (pinfunction "VSS_109") (pintype "unspecified+no_connect"))
    )
    (net (code "183") (name "unconnected-(U9-VSS-Pad113)") (class "Default")
      (node (ref "U9") (pin "113") (pinfunction "VSS_113") (pintype "unspecified+no_connect"))
    )
    (net (code "184") (name "unconnected-(U9-VSS-Pad119)") (class "Default")
      (node (ref "U9") (pin "119") (pinfunction "VSS_119") (pintype "unspecified+no_connect"))
    )
    (net (code "185") (name "unconnected-(U9-VSS-Pad125)") (class "Default")
      (node (ref "U9") (pin "125") (pinfunction "VSS_125") (pintype "unspecified+no_connect"))
    )
    (net (code "186") (name "unconnected-(U9-VSS-Pad128)") (class "Default")
      (node (ref "U9") (pin "128") (pinfunction "VSS_128") (pintype "unspecified+no_connect"))
    )
    (net (code "187") (name "unconnected-(U9-VSS-Pad132)") (class "Default")
      (node (ref "U9") (pin "132") (pinfunction "VSS_132") (pintype "unspecified+no_connect"))
    )
    (net (code "188") (name "unconnected-(U9-VSS-Pad134)") (class "Default")
      (node (ref "U9") (pin "134") (pinfunction "VSS_134") (pintype "unspecified+no_connect"))
    )
    (net (code "189") (name "unconnected-(U9-VSS-Pad136)") (class "Default")
      (node (ref "U9") (pin "136") (pinfunction "VSS_136") (pintype "unspecified+no_connect"))
    )
    (net (code "190") (name "unconnected-(U9-VSS-Pad138)") (class "Default")
      (node (ref "U9") (pin "138") (pinfunction "VSS_138") (pintype "unspecified+no_connect"))
    )
    (net (code "191") (name "unconnected-(U9-VSS-Pad140)") (class "Default")
      (node (ref "U9") (pin "140") (pinfunction "VSS_140") (pintype "unspecified+no_connect"))
    )
    (net (code "192") (name "unconnected-(U9-VSS-Pad142)") (class "Default")
      (node (ref "U9") (pin "142") (pinfunction "VSS_142") (pintype "unspecified+no_connect"))
    )
    (net (code "193") (name "unconnected-(U9-VSS-Pad145)") (class "Default")
      (node (ref "U9") (pin "145") (pinfunction "VSS_145") (pintype "unspecified+no_connect"))
    )
    (net (code "194") (name "unconnected-(U9-VSS-Pad150)") (class "Default")
      (node (ref "U9") (pin "150") (pinfunction "VSS_150") (pintype "unspecified+no_connect"))
    )
    (net (code "195") (name "unconnected-(U9-VSS-Pad154)") (class "Default")
      (node (ref "U9") (pin "154") (pinfunction "VSS_154") (pintype "unspecified+no_connect"))
    )
    (net (code "196") (name "unconnected-(U9-VSS-Pad156)") (class "Default")
      (node (ref "U9") (pin "156") (pinfunction "VSS_156") (pintype "unspecified+no_connect"))
    )
    (net (code "197") (name "unconnected-(U9-VSS-Pad158)") (class "Default")
      (node (ref "U9") (pin "158") (pinfunction "VSS_158") (pintype "unspecified+no_connect"))
    )
    (net (code "198") (name "unconnected-(U9-VSS-Pad160)") (class "Default")
      (node (ref "U9") (pin "160") (pinfunction "VSS_160") (pintype "unspecified+no_connect"))
    )
  )
)
